# SCH_4-Digit-Counter_2024-08-14.net
KiCad netlist of a schematic drawn in EasyEDA
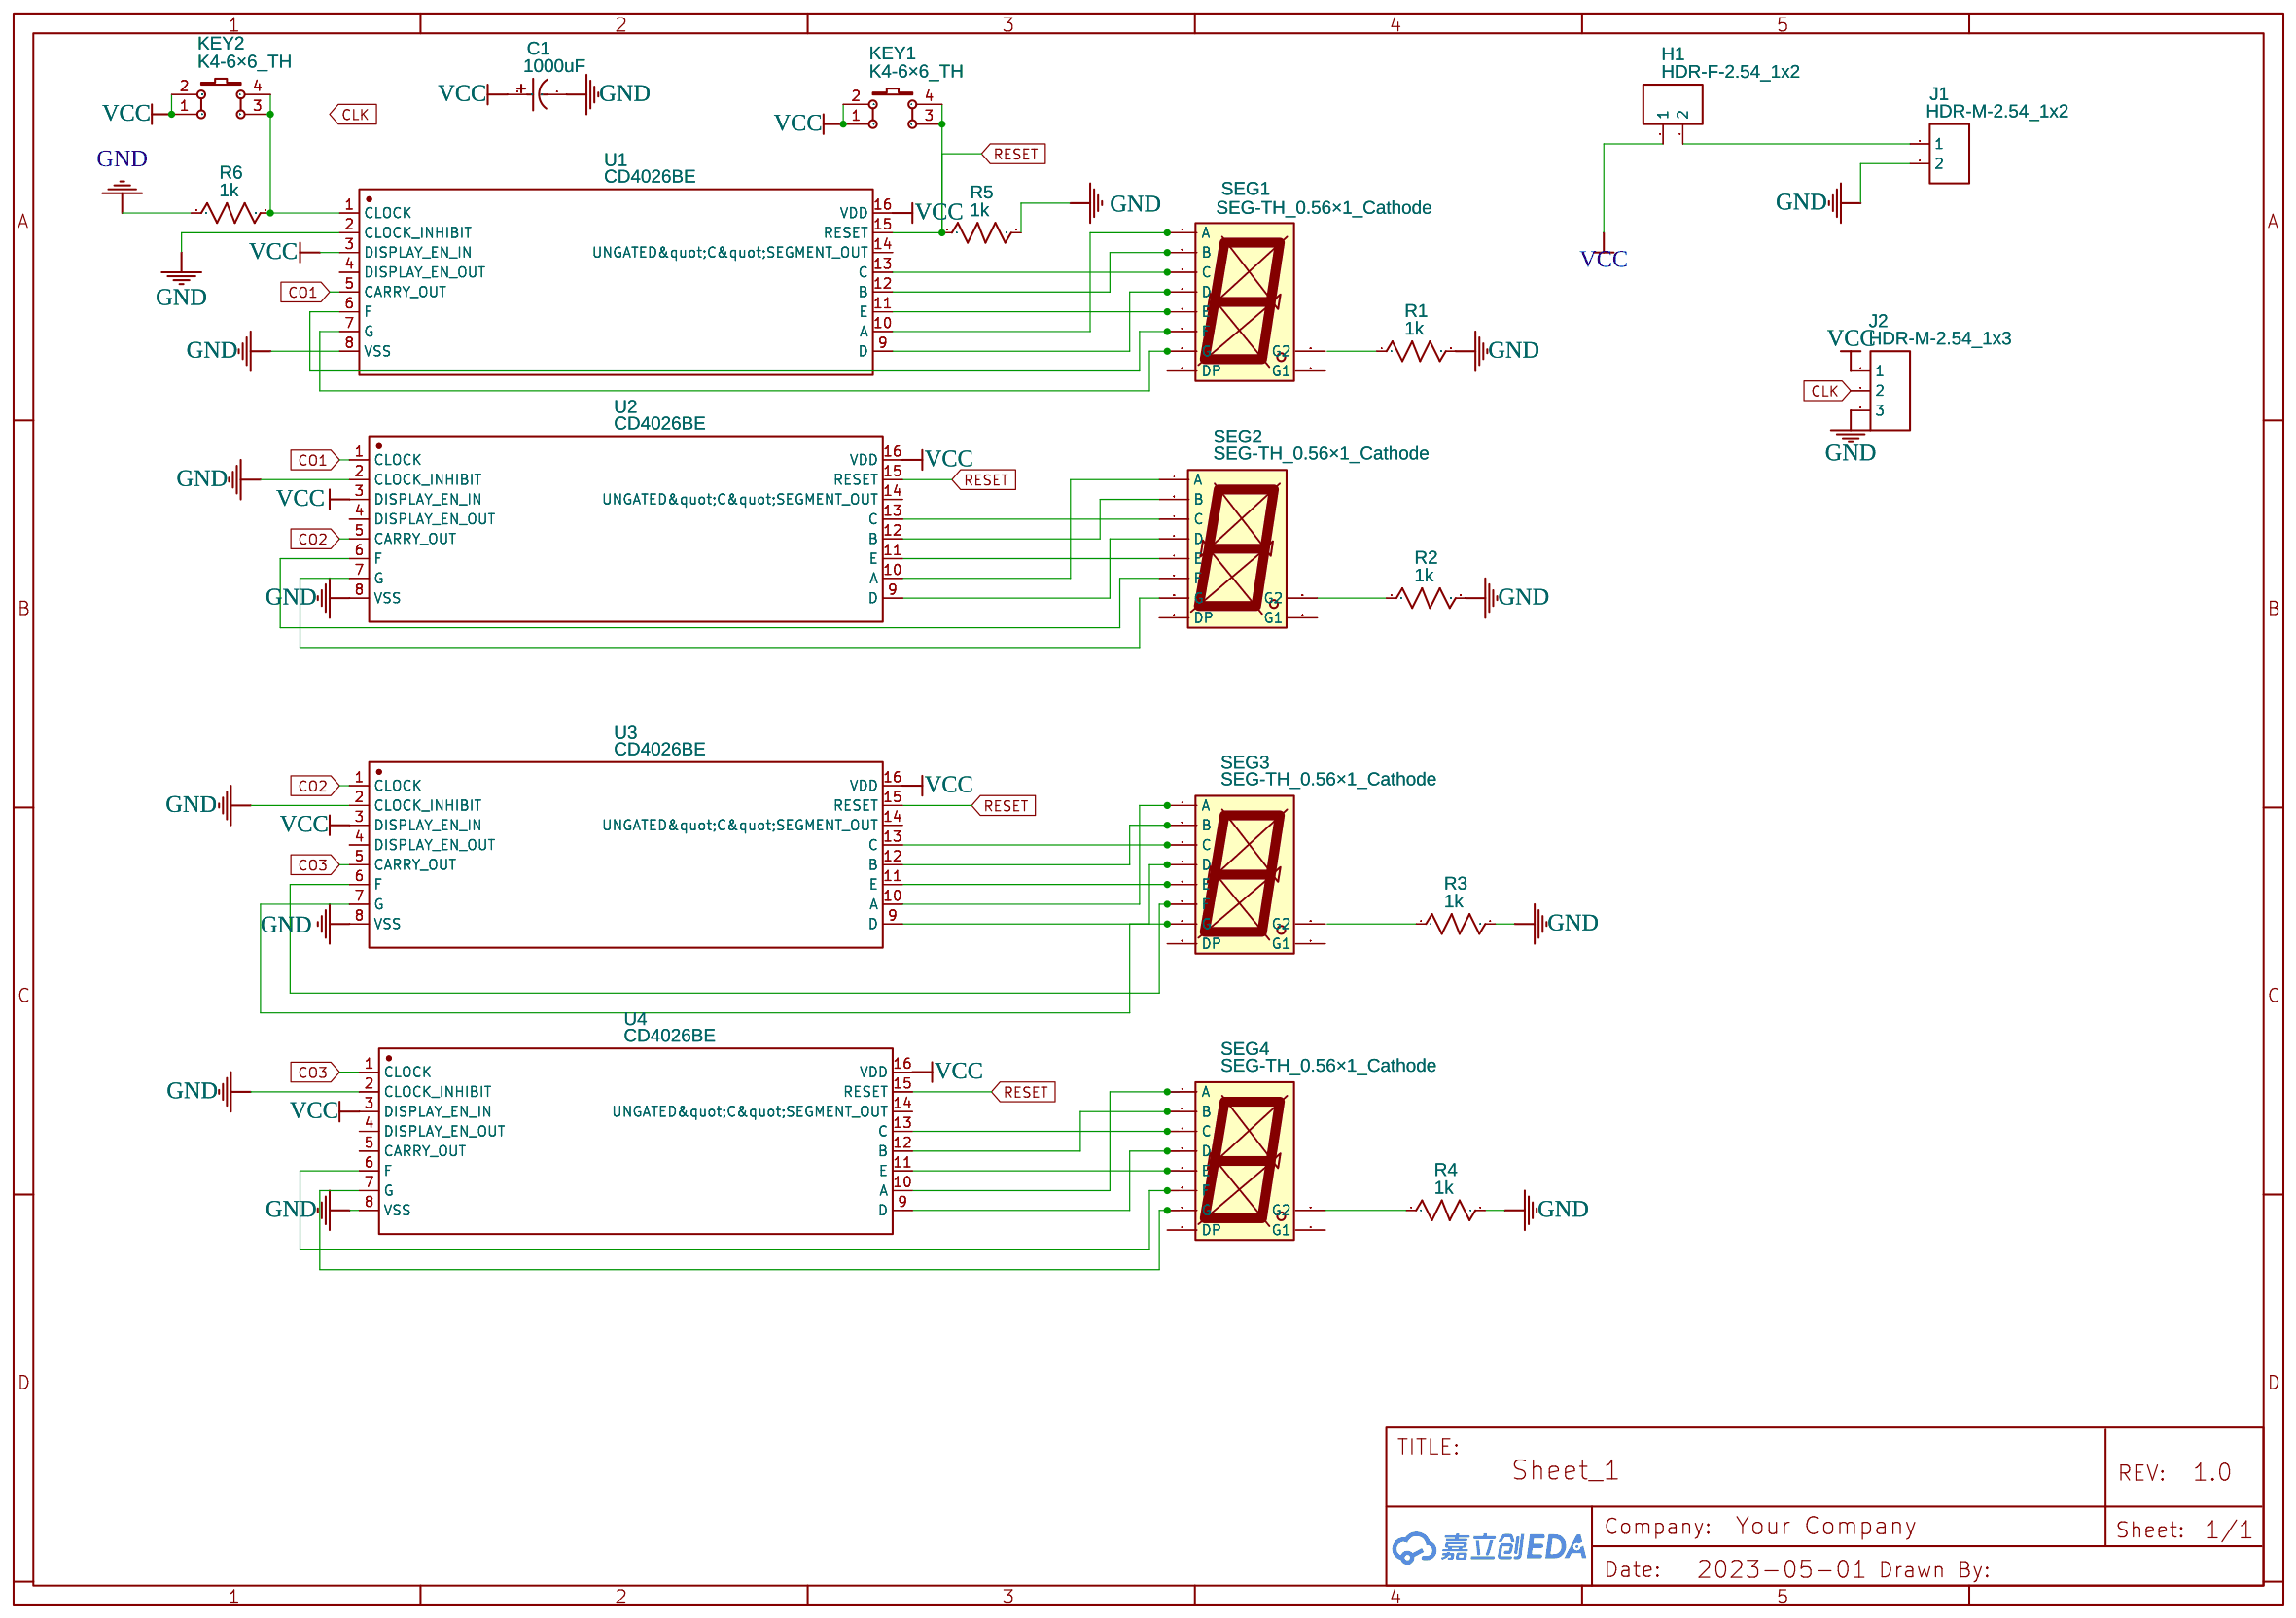
[diagram p0: schematic sheet]

(export (version "E")
  (design (tool "Eeschema 10.0.6"))
  (components
    (comp (ref "C1")
      (value "1000uF")
      (fields
        (field (name "Manufacturer Part") "KM108M016G13RR0VH2FP0")
        (field (name "Manufacturer") "CX(承兴)")
      )
      (libsource (lib "") (part "1000uF 16V 10*13"))
    )
    (comp (ref "H1") (value "HDR-F-2.54_1x2") (libsource (lib "") (part "HDR-F-2.54_1x2")))
    (comp (ref "J1") (value "HDR-M-2.54_1x2") (libsource (lib "") (part "HDR-M-2.54_1x2")))
    (comp (ref "J2") (value "HDR-M-2.54_1x3") (libsource (lib "") (part "HDR-M-2.54_1x3")))
    (comp (ref "KEY1")
      (value "K4-6×6_TH")
      (fields (field (name "Manufacturer Part") "K2-1102DP-E4SW-04") (field (name "Manufacturer") "韩国韩荣"))
      (libsource (lib "") (part "K4-6×6_TH"))
    )
    (comp (ref "KEY2")
      (value "K4-6×6_TH")
      (fields (field (name "Manufacturer Part") "K2-1102DP-E4SW-04") (field (name "Manufacturer") "韩国韩荣"))
      (libsource (lib "") (part "K4-6×6_TH"))
    )
    (comp (ref "R1") (value "1k") (libsource (lib "") (part "R_AXIAL-0.4_US")))
    (comp (ref "R2") (value "1k") (libsource (lib "") (part "R_AXIAL-0.4_US")))
    (comp (ref "R3") (value "1k") (libsource (lib "") (part "R_AXIAL-0.4_US")))
    (comp (ref "R4") (value "1k") (libsource (lib "") (part "R_AXIAL-0.4_US")))
    (comp (ref "R5") (value "1k") (libsource (lib "") (part "R_AXIAL-0.4_US")))
    (comp (ref "R6") (value "1k") (libsource (lib "") (part "R_AXIAL-0.4_US")))
    (comp (ref "SEG1")
      (value "SEG-TH_0.56×1_Cathode")
      (fields (field (name "Manufacturer") "志浩"))
      (libsource (lib "") (part "SEG-TH_0.56×1_Cathode_1"))
    )
    (comp (ref "SEG2")
      (value "SEG-TH_0.56×1_Cathode")
      (fields (field (name "Manufacturer") "志浩"))
      (libsource (lib "") (part "SEG-TH_0.56×1_Cathode"))
    )
    (comp (ref "SEG3")
      (value "SEG-TH_0.56×1_Cathode")
      (fields (field (name "Manufacturer") "志浩"))
      (libsource (lib "") (part "SEG-TH_0.56×1_Cathode_1"))
    )
    (comp (ref "SEG4")
      (value "SEG-TH_0.56×1_Cathode")
      (fields (field (name "Manufacturer") "志浩"))
      (libsource (lib "") (part "SEG-TH_0.56×1_Cathode_1"))
    )
    (comp (ref "U1")
      (value "CD4026BE")
      (fields (field (name "Manufacturer") "TI(德州仪器)"))
      (libsource (lib "") (part "CD4026BE"))
    )
    (comp (ref "U2")
      (value "CD4026BE")
      (fields (field (name "Manufacturer") "TI(德州仪器)"))
      (libsource (lib "") (part "CD4026BE"))
    )
    (comp (ref "U3")
      (value "CD4026BE")
      (fields (field (name "Manufacturer") "TI(德州仪器)"))
      (libsource (lib "") (part "CD4026BE"))
    )
    (comp (ref "U4")
      (value "CD4026BE")
      (fields (field (name "Manufacturer") "TI(德州仪器)"))
      (libsource (lib "") (part "CD4026BE"))
    )
  )
  (nets
    (net (code "1") (name "CLK") (class "Default")
      (node (ref "J2") (pin "2") (pinfunction "2_2") (pintype "input"))
    )
    (net (code "2") (name "CO1") (class "Default")
      (node (ref "U1") (pin "5") (pinfunction "CARRY_OUT_5") (pintype "unspecified"))
      (node (ref "U2") (pin "1") (pinfunction "CLOCK_1") (pintype "unspecified"))
    )
    (net (code "3") (name "CO2") (class "Default")
      (node (ref "U2") (pin "5") (pinfunction "CARRY_OUT_5") (pintype "unspecified"))
      (node (ref "U3") (pin "1") (pinfunction "CLOCK_1") (pintype "unspecified"))
    )
    (net (code "4") (name "CO3") (class "Default")
      (node (ref "U3") (pin "5") (pinfunction "CARRY_OUT_5") (pintype "unspecified"))
      (node (ref "U4") (pin "1") (pinfunction "CLOCK_1") (pintype "unspecified"))
    )
    (net (code "5") (name "GND") (class "Default")
      (node (ref "C1") (pin "2") (pinfunction "2_2") (pintype "input"))
      (node (ref "J1") (pin "2") (pinfunction "2_2") (pintype "unspecified"))
      (node (ref "J2") (pin "3") (pinfunction "3_3") (pintype "input"))
      (node (ref "R1") (pin "2") (pinfunction "2_2") (pintype "unspecified"))
      (node (ref "R2") (pin "2") (pinfunction "2_2") (pintype "unspecified"))
      (node (ref "R3") (pin "2") (pinfunction "2_2") (pintype "unspecified"))
      (node (ref "R4") (pin "2") (pinfunction "2_2") (pintype "unspecified"))
      (node (ref "R5") (pin "2") (pinfunction "2_2") (pintype "unspecified"))
      (node (ref "R6") (pin "1") (pinfunction "1_1") (pintype "unspecified"))
      (node (ref "U1") (pin "2") (pinfunction "CLOCK_INHIBIT_2") (pintype "unspecified"))
      (node (ref "U1") (pin "8") (pinfunction "VSS_8") (pintype "unspecified"))
      (node (ref "U2") (pin "2") (pinfunction "CLOCK_INHIBIT_2") (pintype "unspecified"))
      (node (ref "U2") (pin "8") (pinfunction "VSS_8") (pintype "unspecified"))
      (node (ref "U3") (pin "2") (pinfunction "CLOCK_INHIBIT_2") (pintype "unspecified"))
      (node (ref "U3") (pin "8") (pinfunction "VSS_8") (pintype "unspecified"))
      (node (ref "U4") (pin "2") (pinfunction "CLOCK_INHIBIT_2") (pintype "unspecified"))
      (node (ref "U4") (pin "8") (pinfunction "VSS_8") (pintype "unspecified"))
    )
    (net (code "6") (name "Net-(H1-Pad2)") (class "Default")
      (node (ref "H1") (pin "2") (pinfunction "2_2") (pintype "input"))
      (node (ref "J1") (pin "1") (pinfunction "1_1") (pintype "unspecified"))
    )
    (net (code "7") (name "Net-(SEG1-A)") (class "Default")
      (node (ref "SEG1") (pin "7") (pinfunction "A_7") (pintype "unspecified"))
      (node (ref "U1") (pin "10") (pinfunction "A_10") (pintype "unspecified"))
    )
    (net (code "8") (name "Net-(SEG1-B)") (class "Default")
      (node (ref "SEG1") (pin "6") (pinfunction "B_6") (pintype "unspecified"))
      (node (ref "U1") (pin "12") (pinfunction "B_12") (pintype "unspecified"))
    )
    (net (code "9") (name "Net-(SEG1-C)") (class "Default")
      (node (ref "SEG1") (pin "4") (pinfunction "C_4") (pintype "unspecified"))
      (node (ref "U1") (pin "13") (pinfunction "C_13") (pintype "unspecified"))
    )
    (net (code "10") (name "Net-(SEG1-D)") (class "Default")
      (node (ref "SEG1") (pin "2") (pinfunction "D_2") (pintype "unspecified"))
      (node (ref "U1") (pin "9") (pinfunction "D_9") (pintype "unspecified"))
    )
    (net (code "11") (name "Net-(SEG1-E)") (class "Default")
      (node (ref "SEG1") (pin "1") (pinfunction "E_1") (pintype "unspecified"))
      (node (ref "U1") (pin "11") (pinfunction "E_11") (pintype "unspecified"))
    )
    (net (code "12") (name "Net-(SEG1-F)") (class "Default")
      (node (ref "SEG1") (pin "9") (pinfunction "F_9") (pintype "unspecified"))
      (node (ref "U1") (pin "6") (pinfunction "F_6") (pintype "unspecified"))
    )
    (net (code "13") (name "Net-(SEG1-G)") (class "Default")
      (node (ref "SEG1") (pin "10") (pinfunction "G_10") (pintype "unspecified"))
      (node (ref "U1") (pin "7") (pinfunction "G_7") (pintype "unspecified"))
    )
    (net (code "14") (name "Net-(SEG2-A)") (class "Default")
      (node (ref "SEG2") (pin "7") (pinfunction "A_7") (pintype "unspecified"))
      (node (ref "U2") (pin "10") (pinfunction "A_10") (pintype "unspecified"))
    )
    (net (code "15") (name "Net-(SEG2-B)") (class "Default")
      (node (ref "SEG2") (pin "6") (pinfunction "B_6") (pintype "unspecified"))
      (node (ref "U2") (pin "12") (pinfunction "B_12") (pintype "unspecified"))
    )
    (net (code "16") (name "Net-(SEG2-C)") (class "Default")
      (node (ref "SEG2") (pin "4") (pinfunction "C_4") (pintype "unspecified"))
      (node (ref "U2") (pin "13") (pinfunction "C_13") (pintype "unspecified"))
    )
    (net (code "17") (name "Net-(SEG2-D)") (class "Default")
      (node (ref "SEG2") (pin "2") (pinfunction "D_2") (pintype "unspecified"))
      (node (ref "U2") (pin "9") (pinfunction "D_9") (pintype "unspecified"))
    )
    (net (code "18") (name "Net-(SEG2-E)") (class "Default")
      (node (ref "SEG2") (pin "1") (pinfunction "E_1") (pintype "unspecified"))
      (node (ref "U2") (pin "11") (pinfunction "E_11") (pintype "unspecified"))
    )
    (net (code "19") (name "Net-(SEG2-F)") (class "Default")
      (node (ref "SEG2") (pin "9") (pinfunction "F_9") (pintype "unspecified"))
      (node (ref "U2") (pin "6") (pinfunction "F_6") (pintype "unspecified"))
    )
    (net (code "20") (name "Net-(SEG2-G)") (class "Default")
      (node (ref "SEG2") (pin "10") (pinfunction "G_10") (pintype "unspecified"))
      (node (ref "U2") (pin "7") (pinfunction "G_7") (pintype "unspecified"))
    )
    (net (code "21") (name "Net-(SEG2-G2)") (class "Default")
      (node (ref "R2") (pin "1") (pinfunction "1_1") (pintype "unspecified"))
      (node (ref "SEG2") (pin "8") (pinfunction "G2_8") (pintype "unspecified"))
    )
    (net (code "22") (name "Net-(SEG3-A)") (class "Default")
      (node (ref "SEG3") (pin "7") (pinfunction "A_7") (pintype "unspecified"))
      (node (ref "U3") (pin "10") (pinfunction "A_10") (pintype "unspecified"))
    )
    (net (code "23") (name "Net-(SEG3-B)") (class "Default")
      (node (ref "SEG3") (pin "6") (pinfunction "B_6") (pintype "unspecified"))
      (node (ref "U3") (pin "12") (pinfunction "B_12") (pintype "unspecified"))
    )
    (net (code "24") (name "Net-(SEG3-C)") (class "Default")
      (node (ref "SEG3") (pin "4") (pinfunction "C_4") (pintype "unspecified"))
      (node (ref "U3") (pin "13") (pinfunction "C_13") (pintype "unspecified"))
    )
    (net (code "25") (name "Net-(SEG3-D)") (class "Default")
      (node (ref "SEG3") (pin "2") (pinfunction "D_2") (pintype "unspecified"))
      (node (ref "U3") (pin "9") (pinfunction "D_9") (pintype "unspecified"))
    )
    (net (code "26") (name "Net-(SEG3-E)") (class "Default")
      (node (ref "SEG3") (pin "1") (pinfunction "E_1") (pintype "unspecified"))
      (node (ref "U3") (pin "11") (pinfunction "E_11") (pintype "unspecified"))
    )
    (net (code "27") (name "Net-(SEG3-F)") (class "Default")
      (node (ref "SEG3") (pin "9") (pinfunction "F_9") (pintype "unspecified"))
      (node (ref "U3") (pin "6") (pinfunction "F_6") (pintype "unspecified"))
    )
    (net (code "28") (name "Net-(SEG3-G)") (class "Default")
      (node (ref "SEG3") (pin "10") (pinfunction "G_10") (pintype "unspecified"))
      (node (ref "U3") (pin "7") (pinfunction "G_7") (pintype "unspecified"))
    )
    (net (code "29") (name "Net-(SEG4-A)") (class "Default")
      (node (ref "SEG4") (pin "7") (pinfunction "A_7") (pintype "unspecified"))
      (node (ref "U4") (pin "10") (pinfunction "A_10") (pintype "unspecified"))
    )
    (net (code "30") (name "Net-(SEG4-B)") (class "Default")
      (node (ref "SEG4") (pin "6") (pinfunction "B_6") (pintype "unspecified"))
      (node (ref "U4") (pin "12") (pinfunction "B_12") (pintype "unspecified"))
    )
    (net (code "31") (name "Net-(SEG4-C)") (class "Default")
      (node (ref "SEG4") (pin "4") (pinfunction "C_4") (pintype "unspecified"))
      (node (ref "U4") (pin "13") (pinfunction "C_13") (pintype "unspecified"))
    )
    (net (code "32") (name "Net-(SEG4-D)") (class "Default")
      (node (ref "SEG4") (pin "2") (pinfunction "D_2") (pintype "unspecified"))
      (node (ref "U4") (pin "9") (pinfunction "D_9") (pintype "unspecified"))
    )
    (net (code "33") (name "Net-(SEG4-E)") (class "Default")
      (node (ref "SEG4") (pin "1") (pinfunction "E_1") (pintype "unspecified"))
      (node (ref "U4") (pin "11") (pinfunction "E_11") (pintype "unspecified"))
    )
    (net (code "34") (name "Net-(SEG4-F)") (class "Default")
      (node (ref "SEG4") (pin "9") (pinfunction "F_9") (pintype "unspecified"))
      (node (ref "U4") (pin "6") (pinfunction "F_6") (pintype "unspecified"))
    )
    (net (code "35") (name "Net-(SEG4-G)") (class "Default")
      (node (ref "SEG4") (pin "10") (pinfunction "G_10") (pintype "unspecified"))
      (node (ref "U4") (pin "7") (pinfunction "G_7") (pintype "unspecified"))
    )
    (net (code "36") (name "Net-(SEG4-G2)") (class "Default")
      (node (ref "R4") (pin "1") (pinfunction "1_1") (pintype "unspecified"))
      (node (ref "SEG4") (pin "8") (pinfunction "G2_8") (pintype "unspecified"))
    )
    (net (code "37") (name "Net-(U1-CLOCK)") (class "Default")
      (node (ref "KEY2") (pin "3") (pinfunction "3_3") (pintype "unspecified"))
      (node (ref "KEY2") (pin "4") (pinfunction "4_4") (pintype "unspecified"))
      (node (ref "R6") (pin "2") (pinfunction "2_2") (pintype "unspecified"))
      (node (ref "U1") (pin "1") (pinfunction "CLOCK_1") (pintype "unspecified"))
    )
    (net (code "38") (name "RESET") (class "Default")
      (node (ref "KEY1") (pin "3") (pinfunction "3_3") (pintype "unspecified"))
      (node (ref "KEY1") (pin "4") (pinfunction "4_4") (pintype "unspecified"))
      (node (ref "R5") (pin "1") (pinfunction "1_1") (pintype "unspecified"))
      (node (ref "U1") (pin "15") (pinfunction "RESET_15") (pintype "unspecified"))
      (node (ref "U2") (pin "15") (pinfunction "RESET_15") (pintype "unspecified"))
      (node (ref "U3") (pin "15") (pinfunction "RESET_15") (pintype "unspecified"))
      (node (ref "U4") (pin "15") (pinfunction "RESET_15") (pintype "unspecified"))
    )
    (net (code "39") (name "VCC") (class "Default")
      (node (ref "C1") (pin "1") (pinfunction "1_1") (pintype "input"))
      (node (ref "H1") (pin "1") (pinfunction "1_1") (pintype "input"))
      (node (ref "J2") (pin "1") (pinfunction "1_1") (pintype "input"))
      (node (ref "KEY1") (pin "1") (pinfunction "1_1") (pintype "unspecified"))
      (node (ref "KEY1") (pin "2") (pinfunction "2_2") (pintype "unspecified"))
      (node (ref "KEY2") (pin "1") (pinfunction "1_1") (pintype "unspecified"))
      (node (ref "KEY2") (pin "2") (pinfunction "2_2") (pintype "unspecified"))
      (node (ref "U1") (pin "16") (pinfunction "VDD_16") (pintype "unspecified"))
      (node (ref "U1") (pin "3") (pinfunction "DISPLAY_EN_IN_3") (pintype "unspecified"))
      (node (ref "U2") (pin "16") (pinfunction "VDD_16") (pintype "unspecified"))
      (node (ref "U2") (pin "3") (pinfunction "DISPLAY_EN_IN_3") (pintype "unspecified"))
      (node (ref "U3") (pin "16") (pinfunction "VDD_16") (pintype "unspecified"))
      (node (ref "U3") (pin "3") (pinfunction "DISPLAY_EN_IN_3") (pintype "unspecified"))
      (node (ref "U4") (pin "16") (pinfunction "VDD_16") (pintype "unspecified"))
      (node (ref "U4") (pin "3") (pinfunction "DISPLAY_EN_IN_3") (pintype "unspecified"))
    )
    (net (code "40") (name "unconnected-(R1-Pad1)") (class "Default")
      (node (ref "R1") (pin "1") (pinfunction "1_1") (pintype "unspecified"))
    )
    (net (code "41") (name "unconnected-(R3-Pad1)") (class "Default")
      (node (ref "R3") (pin "1") (pinfunction "1_1") (pintype "unspecified"))
    )
    (net (code "42") (name "unconnected-(SEG1-DP-Pad5)") (class "Default")
      (node (ref "SEG1") (pin "5") (pinfunction "DP_5") (pintype "unspecified"))
    )
    (net (code "43") (name "unconnected-(SEG1-G1-Pad3)") (class "Default")
      (node (ref "SEG1") (pin "3") (pinfunction "G1_3") (pintype "unspecified"))
    )
    (net (code "44") (name "unconnected-(SEG1-G2-Pad8)") (class "Default")
      (node (ref "SEG1") (pin "8") (pinfunction "G2_8") (pintype "unspecified"))
    )
    (net (code "45") (name "unconnected-(SEG2-DP-Pad5)") (class "Default")
      (node (ref "SEG2") (pin "5") (pinfunction "DP_5") (pintype "unspecified"))
    )
    (net (code "46") (name "unconnected-(SEG2-G1-Pad3)") (class "Default")
      (node (ref "SEG2") (pin "3") (pinfunction "G1_3") (pintype "unspecified"))
    )
    (net (code "47") (name "unconnected-(SEG3-DP-Pad5)") (class "Default")
      (node (ref "SEG3") (pin "5") (pinfunction "DP_5") (pintype "unspecified"))
    )
    (net (code "48") (name "unconnected-(SEG3-G1-Pad3)") (class "Default")
      (node (ref "SEG3") (pin "3") (pinfunction "G1_3") (pintype "unspecified"))
    )
    (net (code "49") (name "unconnected-(SEG3-G2-Pad8)") (class "Default")
      (node (ref "SEG3") (pin "8") (pinfunction "G2_8") (pintype "unspecified"))
    )
    (net (code "50") (name "unconnected-(SEG4-DP-Pad5)") (class "Default")
      (node (ref "SEG4") (pin "5") (pinfunction "DP_5") (pintype "unspecified"))
    )
    (net (code "51") (name "unconnected-(SEG4-G1-Pad3)") (class "Default")
      (node (ref "SEG4") (pin "3") (pinfunction "G1_3") (pintype "unspecified"))
    )
    (net (code "52") (name "unconnected-(U1-DISPLAY_EN_OUT-Pad4)") (class "Default")
      (node (ref "U1") (pin "4") (pinfunction "DISPLAY_EN_OUT_4") (pintype "unspecified"))
    )
    (net (code "53") (name "unconnected-(U1-UNGATED&quot;C&quot;SEGMENT_OUT-Pad14)") (class "Default")
      (node (ref "U1") (pin "14") (pinfunction "UNGATED&quot;C&quot;SEGMENT_OUT_14") (pintype "unspecified"))
    )
    (net (code "54") (name "unconnected-(U2-DISPLAY_EN_OUT-Pad4)") (class "Default")
      (node (ref "U2") (pin "4") (pinfunction "DISPLAY_EN_OUT_4") (pintype "unspecified"))
    )
    (net (code "55") (name "unconnected-(U2-UNGATED&quot;C&quot;SEGMENT_OUT-Pad14)") (class "Default")
      (node (ref "U2") (pin "14") (pinfunction "UNGATED&quot;C&quot;SEGMENT_OUT_14") (pintype "unspecified"))
    )
    (net (code "56") (name "unconnected-(U3-DISPLAY_EN_OUT-Pad4)") (class "Default")
      (node (ref "U3") (pin "4") (pinfunction "DISPLAY_EN_OUT_4") (pintype "unspecified"))
    )
    (net (code "57") (name "unconnected-(U3-UNGATED&quot;C&quot;SEGMENT_OUT-Pad14)") (class "Default")
      (node (ref "U3") (pin "14") (pinfunction "UNGATED&quot;C&quot;SEGMENT_OUT_14") (pintype "unspecified"))
    )
    (net (code "58") (name "unconnected-(U4-CARRY_OUT-Pad5)") (class "Default")
      (node (ref "U4") (pin "5") (pinfunction "CARRY_OUT_5") (pintype "unspecified"))
    )
    (net (code "59") (name "unconnected-(U4-DISPLAY_EN_OUT-Pad4)") (class "Default")
      (node (ref "U4") (pin "4") (pinfunction "DISPLAY_EN_OUT_4") (pintype "unspecified"))
    )
    (net (code "60") (name "unconnected-(U4-UNGATED&quot;C&quot;SEGMENT_OUT-Pad14)") (class "Default")
      (node (ref "U4") (pin "14") (pinfunction "UNGATED&quot;C&quot;SEGMENT_OUT_14") (pintype "unspecified"))
    )
  )
)
